# 04_Incense_MCU.net
KiCad netlist of a schematic drawn in Altium Designer
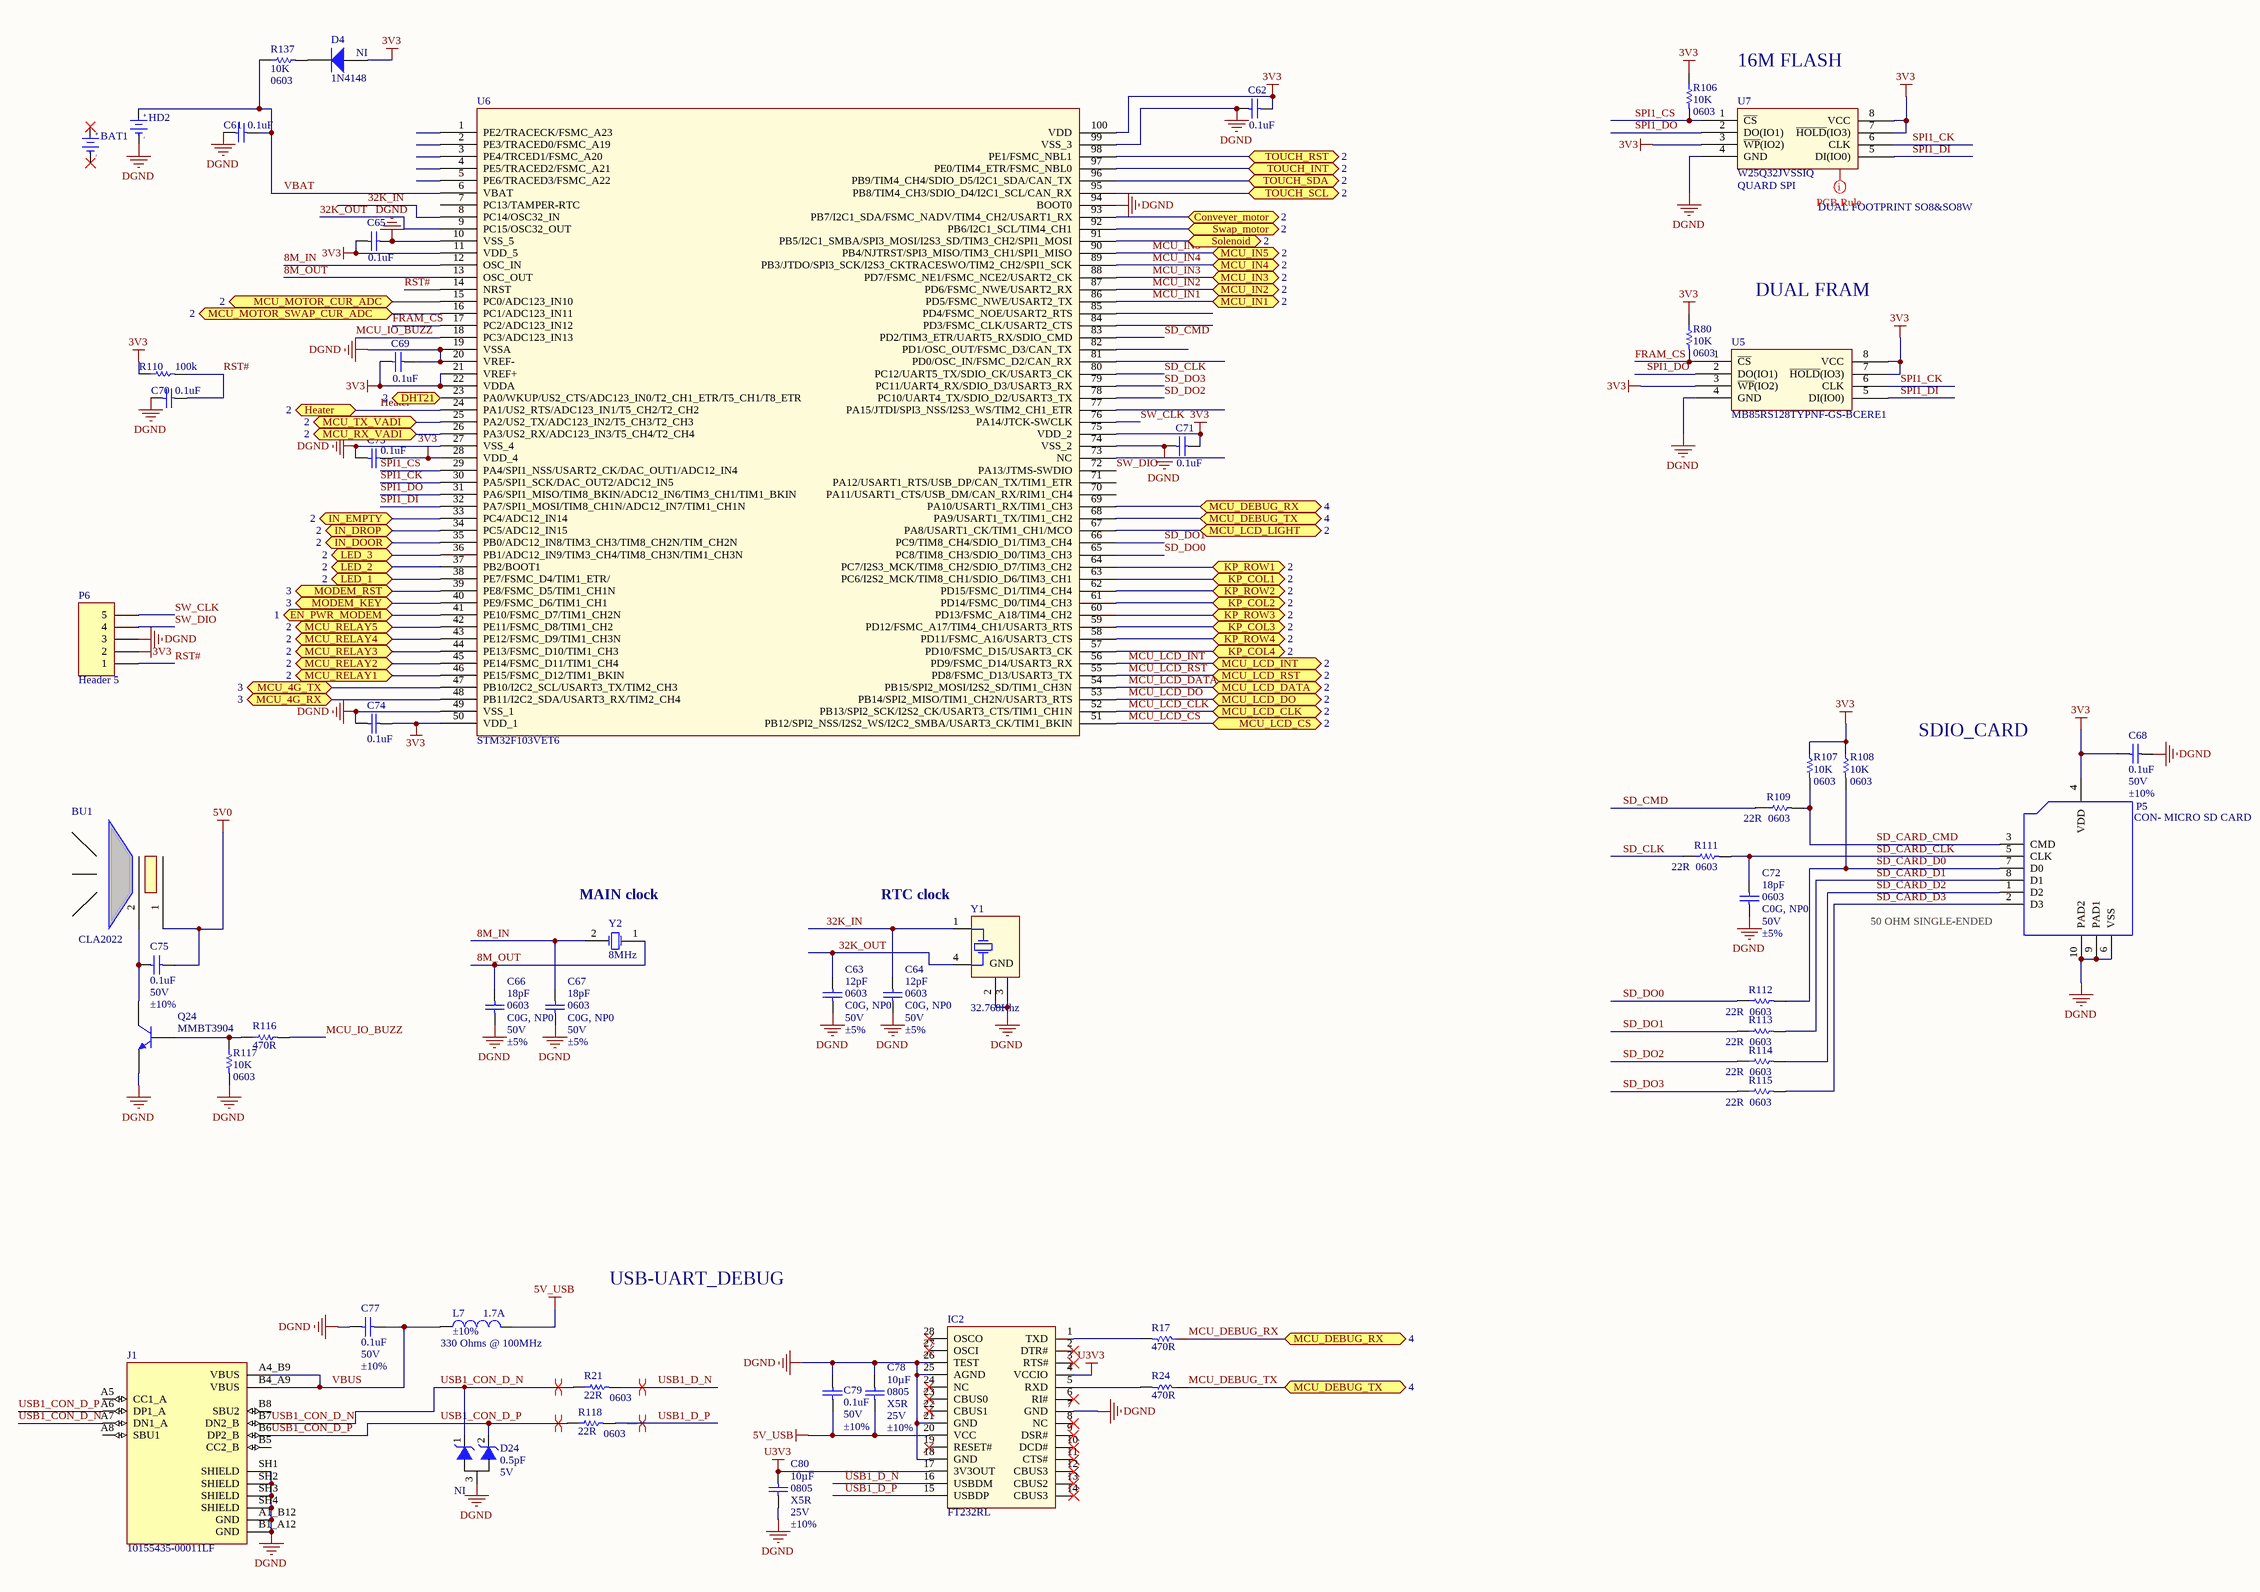
[diagram p0: 04_Incense_MCU.SchDoc]

(export (version "E")
  (design (tool "Eeschema 10.0.6"))
  (components
    (comp (ref "BAT1")
      (value "CR1220")
      (footprint "De Pin Cr1220")
      (description "CR1220 BATTERY")
      (fields (field (name "MANUFACTURER1_PART#") "PIN CR1220 Lithium"))
      (libsource (lib "Schlib1") (part "CR1220 SMD"))
    )
    (comp (ref "BU1")
      (value "CLA2022")
      (footprint "BUZZ_5V_D12X7.5MM")
      (description "BUZZ 5V 12095 12x9.5mm")
      (fields (field (name "MANUFACTURER2_PART#") "5V 9.5x12MM"))
      (libsource (lib "VSM_SES-MAIN_REV04B") (part "PKM13EPYH4000"))
    )
    (comp (ref "C61")
      (value "0.1uF,0805,16v")
      (footprint "CAP 0603")
      (description "CAP CER 0.1UF 50V X7R 0603")
      (fields
        (field (name "=VALUE") "0.1uF")
        (field (name "MANUFACTURER1_PART#") "CL10B104KB8NNNC")
        (field (name "PUBLISHER") "Altium Limited")
      )
      (libsource (lib "Miscellaneous Devices") (part "Cap"))
    )
    (comp (ref "C62")
      (value "Cap")
      (footprint "CAP 0603")
      (description "CAP CER 0.1UF 50V X7R 0603")
      (fields
        (field (name "=VALUE") "0.1uF")
        (field (name "MANUFACTURER1_PART#") "CL10B104KB8NNNC")
        (field (name "PUBLISHER") "Altium Limited")
      )
      (libsource (lib "Miscellaneous Devices") (part "Cap"))
    )
    (comp (ref "C63")
      (value "12pF")
      (footprint "0603")
      (description "CAP-CER,SMD;12PF,5%,50V,C0G/NPO 0603")
      (fields
        (field (name "MATERIAL") "C0G, NP0")
        (field (name "VOLTAGE") "50V")
        (field (name "TOLERANCE") "±5%")
        (field (name "MANUFACTURER1_PART#") "CC0603JRNPO9BN120")
      )
      (libsource (lib "Slider") (part "Cap"))
    )
    (comp (ref "C64")
      (value "12pF")
      (footprint "0603")
      (description "CAP-CER,SMD;12PF,5%,50V,C0G/NPO 0603")
      (fields
        (field (name "MATERIAL") "C0G, NP0")
        (field (name "VOLTAGE") "50V")
        (field (name "TOLERANCE") "±5%")
        (field (name "MANUFACTURER1_PART#") "CC0603JRNPO9BN120")
      )
      (libsource (lib "Slider") (part "Cap"))
    )
    (comp (ref "C65")
      (value "Cap")
      (footprint "cap 0603")
      (description "CAP CER 0.1UF 50V X7R 0603")
      (fields
        (field (name "=VALUE") "0.1uF")
        (field (name "MANUFACTURER1_PART#") "CL10B104KB8NNNC")
        (field (name "PUBLISHER") "Altium Limited")
      )
      (libsource (lib "Miscellaneous Devices") (part "Cap"))
    )
    (comp (ref "C66")
      (value "18pF")
      (footprint "0603")
      (description "CAP CER 18PF 50V C0G/NP0 0603")
      (fields
        (field (name "MATERIAL") "C0G, NP0")
        (field (name "VOLTAGE") "50V")
        (field (name "TOLERANCE") "±5%")
        (field (name "MANUFACTURER1_PART#") "CL10C180JB81PNC")
        (field (name "MANUFACTURER2_PART#") "CC0603JRNPO9BN180")
      )
      (libsource (lib "Slider") (part "Cap"))
    )
    (comp (ref "C67")
      (value "18pF")
      (footprint "0603")
      (description "CAP CER 18PF 50V C0G/NP0 0603")
      (fields
        (field (name "MATERIAL") "C0G, NP0")
        (field (name "VOLTAGE") "50V")
        (field (name "TOLERANCE") "±5%")
        (field (name "MANUFACTURER1_PART#") "CL10C180JB81PNC")
        (field (name "MANUFACTURER2_PART#") "CC0603JRNPO9BN180")
      )
      (libsource (lib "Slider") (part "Cap"))
    )
    (comp (ref "C68")
      (value "0.1uF")
      (footprint "CAP 0603")
      (description "CAP-CER,SMD;0.1UF,10%,50V,X7R,0603")
      (fields
        (field (name "VOLTAGE") "50V")
        (field (name "TOLERANCE") "±10%")
        (field (name "MANUFACTURER1_PART#") "CL10B104KB8NNNC")
        (field (name "MANUFACTURER2_PART#") "M0603X104K050TAX")
      )
      (libsource (lib "Slider") (part "Cap"))
    )
    (comp (ref "C69")
      (value "Cap")
      (footprint "CAP 0603")
      (description "CAP CER 0.1UF 50V X7R 0603")
      (fields
        (field (name "=VALUE") "0.1uF")
        (field (name "MANUFACTURER1_PART#") "CL10B104KB8NNNC")
        (field (name "PUBLISHER") "Altium Limited")
      )
      (libsource (lib "Miscellaneous Devices") (part "Cap"))
    )
    (comp (ref "C70")
      (value "Cap")
      (footprint "CAP 0603")
      (description "CAP CER 0.1UF 50V X7R 0603")
      (fields
        (field (name "=VALUE") "0.1uF")
        (field (name "MANUFACTURER1_PART#") "CL10B104KB8NNNC")
        (field (name "PUBLISHER") "Altium Limited")
      )
      (libsource (lib "Miscellaneous Devices") (part "Cap"))
    )
    (comp (ref "C71")
      (value "0.1uF")
      (footprint "CAP 0603")
      (description "CAP-CER,SMD;0.1UF,10%,50V,X7R,0603")
      (fields
        (field (name "MANUFACTURER1_PART#") "CL10B104KB8NNNC")
        (field (name "Comment") "Cap")
        (field (name "PUBLISHER") "Altium Limited")
      )
      (libsource (lib "Miscellaneous Devices") (part "Cap"))
    )
    (comp (ref "C72")
      (value "18pF")
      (footprint "0603")
      (description "CAP CER 18PF 50V C0G/NP0 0603")
      (fields
        (field (name "MATERIAL") "C0G, NP0")
        (field (name "VOLTAGE") "50V")
        (field (name "TOLERANCE") "±5%")
        (field (name "MANUFACTURER1_PART#") "CL10C180JB81PNC")
        (field (name "MANUFACTURER2_PART#") "CC0603JRNPO9BN180")
      )
      (libsource (lib "Slider") (part "Cap"))
    )
    (comp (ref "C73")
      (value "0.1uF")
      (footprint "CAP 0603")
      (description "CAP-CER,SMD;0.1UF,10%,50V,X7R,0603")
      (fields
        (field (name "MANUFACTURER1_PART#") "CL10B104KB8NNNC")
        (field (name "Comment") "Cap")
        (field (name "PUBLISHER") "Altium Limited")
      )
      (libsource (lib "Miscellaneous Devices") (part "Cap"))
    )
    (comp (ref "C74")
      (value "0.1uF")
      (footprint "CAP 0603")
      (description "CAP-CER,SMD;0.1UF,10%,50V,X7R,0603")
      (fields
        (field (name "MANUFACTURER1_PART#") "CL10B104KB8NNNC")
        (field (name "Comment") "Cap")
        (field (name "PUBLISHER") "Altium Limited")
      )
      (libsource (lib "Miscellaneous Devices") (part "Cap"))
    )
    (comp (ref "C75")
      (value "0.1uF")
      (footprint "CAP 0603")
      (description "CAP-CER,SMD;0.1UF,10%,50V,X7R,0603")
      (fields
        (field (name "VOLTAGE") "50V")
        (field (name "TOLERANCE") "±10%")
        (field (name "MANUFACTURER1_PART#") "CL10B104KB8NNNC")
        (field (name "MANUFACTURER2_PART#") "M0603X104K050TAX")
      )
      (libsource (lib "Slider") (part "Cap"))
    )
    (comp (ref "C77")
      (value "0.1uF")
      (footprint "CAP 0603")
      (description "CAP-CER,SMD;0.1UF,10%,50V,X7R,0603")
      (fields
        (field (name "VOLTAGE") "50V")
        (field (name "TOLERANCE") "±10%")
        (field (name "MANUFACTURER1_PART#") "CL10B104KB8NNNC")
        (field (name "MANUFACTURER2_PART#") "M0603X104K050TAX")
      )
      (libsource (lib "Slider") (part "Cap"))
    )
    (comp (ref "C78")
      (value "10µF")
      (footprint "CAP 0805")
      (description "CAP-CER,SMD;10UF,10%,25V,X5R,0805")
      (fields
        (field (name "MANUFACTURER1_PART#") "TMK212BBJ106KG-T")
        (field (name "MANUFACTURER2_PART#") "CL21A106KAYNNNG")
        (field (name "PACKAGE") "0805")
        (field (name "VOLTAGE") "25V")
        (field (name "TOLERANCE") "±10%")
        (field (name "MATERIAL") "X5R")
      )
      (libsource (lib "Full") (part "Cap-NP-100"))
    )
    (comp (ref "C79")
      (value "0.1uF")
      (footprint "CAP 0603")
      (description "CAP-CER,SMD;0.1UF,10%,50V,X7R,0603")
      (fields
        (field (name "VOLTAGE") "50V")
        (field (name "TOLERANCE") "±10%")
        (field (name "MANUFACTURER1_PART#") "CL10B104KB8NNNC")
        (field (name "MANUFACTURER2_PART#") "M0603X104K050TAX")
      )
      (libsource (lib "Slider") (part "Cap"))
    )
    (comp (ref "C80")
      (value "10µF")
      (footprint "CAP 0805")
      (description "CAP-CER,SMD;10UF,10%,25V,X5R,0805")
      (fields
        (field (name "MANUFACTURER1_PART#") "TMK212BBJ106KG-T")
        (field (name "MANUFACTURER2_PART#") "CL21A106KAYNNNG")
        (field (name "PACKAGE") "0805")
        (field (name "VOLTAGE") "25V")
        (field (name "TOLERANCE") "±10%")
        (field (name "MATERIAL") "X5R")
      )
      (libsource (lib "Full") (part "Cap-NP-100"))
    )
    (comp (ref "D4")
      (value "1N4148")
      (footprint "diode_1206")
      (description "DIODE GP 100V 300MA SOD123 10K")
      (fields
        (field (name "ASSEMBLY") "NI")
        (field (name "MANUFACTURER1_PART#") "1N4148WQ-13-F")
        (field (name "PUBLISHER") "Altium Limited")
      )
      (libsource (lib "Miscellaneous Devices") (part "Diode"))
    )
    (comp (ref "D24")
      (value "ESDR0502BT1G")
      (footprint "SOT-416")
      (description "5V, ESD PROTECTION DEVICES, SOT-23")
      (fields
        (field (name "MANUFACTURER2_PART#") "DF3D6.8MS,LF")
        (field (name "POWER") "320W")
        (field (name "CAPACITANCE") "0.5pF")
        (field (name "VOLTAGE") "5V")
        (field (name "NI_MARK") "NI")
      )
      (libsource (lib "My Library") (part "TVS_DUAL_SIGNAL_5V_SOT23"))
    )
    (comp (ref "HD2")
      (value "CR1220-2ZX")
      (footprint "BATTERY HOLDER CR1220 SMD")
      (description "CR1220 SMD HOLDER")
      (fields (field (name "MANUFACTURER2_PART#") "BH-122A-5"))
      (libsource (lib "Schlib1") (part "CR1220 SMD"))
    )
    (comp (ref "IC2")
      (value "FT232RL")
      (footprint "FT232")
      (description "IC USB FS SERIAL UART 28-SSOP")
      (fields
        (field (name "MANUFACTURER1_PART#") "FT232RL-REEL")
        (field (name "MANUFACTURER2_PART#") "PL2303HX")
      )
      (libsource (lib "PART") (part "PL2303HX"))
    )
    (comp (ref "J1")
      (value "10155435-00011LF")
      (footprint "AMPHENOL_10155435-00011LF")
      (description "USB TYPE C R/A SMT 16PIN")
      (fields (field (name "MF") "Amphenol ICC (FCI)"))
      (libsource (lib "10155435-00011LF") (part "10155435-00011LF"))
    )
    (comp (ref "L7")
      (value "330 Ohms @ 100MHz")
      (footprint "FB 0603")
      (description "FERRITE BEAD 330 OHM 0603 1LN")
      (fields
        (field (name "MANUFACTURER1_PART#") "MPZ1608S331ATA00")
        (field (name "MANUFACTURER2_PART#") "BLM18KG331SN1D")
        (field (name "CURRENT") "1.7A")
        (field (name "TOLERANCE") "±10%")
      )
      (libsource (lib "Full") (part "inductor 2.2uF"))
    )
    (comp (ref "P5")
      (value "CON- MICRO SD CARD")
      (footprint "SD-01A")
      (description "SMD Card Sockets")
      (fields (field (name "MANUFACTURER1_PART#") "SD-01A"))
      (libsource (lib "VDM_V1.0") (part "CON- MICRO SD CARD"))
    )
    (comp (ref "P6")
      (value "Header 5")
      (footprint "HDR1X5")
      (description "Header, 5-Pin,2.54mm")
      (fields (field (name "PUBLISHER") "Altium Limited"))
      (libsource (lib "Miscellaneous Connectors") (part "Header 5"))
    )
    (comp (ref "Q24")
      (value "MMBT3904")
      (footprint "SOT-23")
      (description "NPN 200mA 40V 350mW SOT-23 Transistors")
      (libsource (lib "Miscellaneous Devices") (part "NPN"))
    )
    (comp (ref "R17")
      (value "470R")
      (footprint "res 0603")
      (description "RES SMD, 470 OHM 5% 1/8W 0603")
      (fields
        (field (name "MANUFACTURER1_PART#") "RK73B1JTTD471J")
        (field (name "MANUFACTURER2_PART#") "RMCF0603JT470R")
      )
      (libsource (lib "Full") (part "Res0.3"))
    )
    (comp (ref "R21")
      (value "22R")
      (footprint "res 0603")
      (description "RES 22 OHM 5% 1/10W 0603")
      (fields
        (field (name "MANUFACTURER1_PART#") "RC0603JR-0722RL")
        (field (name "MANUFACTURER2_PART#") "RMCF0603JT22R0")
        (field (name "PCB FOOTPRINT") "0603")
      )
      (libsource (lib "Full") (part "Res0.3"))
    )
    (comp (ref "R24")
      (value "470R")
      (footprint "res 0603")
      (description "RES SMD, 470 OHM 5% 1/8W 0603")
      (fields
        (field (name "MANUFACTURER1_PART#") "RK73B1JTTD471J")
        (field (name "MANUFACTURER2_PART#") "RMCF0603JT470R")
      )
      (libsource (lib "Full") (part "Res0.3"))
    )
    (comp (ref "R80")
      (value "10K")
      (footprint "res 0603")
      (description "RES SMD,10K OHM 5% 1/10W 0603")
      (fields
        (field (name "MANUFACTURER1_PART#") "RMCF0603JT10K0")
        (field (name "MANUFACTURER2_PART#") "R0603J10KKDX")
        (field (name "PCB FOOTPRINT") "0603")
      )
      (libsource (lib "altium-import") (part "root_3_Res0.3_"))
    )
    (comp (ref "R106")
      (value "10K")
      (footprint "res 0603")
      (description "RES SMD,10K OHM 5% 1/10W 0603")
      (fields
        (field (name "MANUFACTURER1_PART#") "RMCF0603JT10K0")
        (field (name "MANUFACTURER2_PART#") "R0603J10KKDX")
        (field (name "PCB FOOTPRINT") "0603")
      )
      (libsource (lib "altium-import") (part "root_3_Res0.3_"))
    )
    (comp (ref "R107")
      (value "10K")
      (footprint "res 0603")
      (description "RES SMD,10K OHM 5% 1/10W 0603")
      (fields
        (field (name "MANUFACTURER1_PART#") "RMCF0603JT10K0")
        (field (name "MANUFACTURER2_PART#") "R0603J10KKDX")
        (field (name "PCB FOOTPRINT") "0603")
      )
      (libsource (lib "altium-import") (part "root_3_Res0.3_"))
    )
    (comp (ref "R108")
      (value "10K")
      (footprint "res 0603")
      (description "RES SMD,10K OHM 5% 1/10W 0603")
      (fields
        (field (name "MANUFACTURER1_PART#") "RMCF0603JT10K0")
        (field (name "MANUFACTURER2_PART#") "R0603J10KKDX")
        (field (name "PCB FOOTPRINT") "0603")
      )
      (libsource (lib "altium-import") (part "root_3_Res0.3_"))
    )
    (comp (ref "R109")
      (value "22R")
      (footprint "res 0603")
      (description "RES 22 OHM 5% 1/10W 0603")
      (fields
        (field (name "MANUFACTURER1_PART#") "RC0603JR-0722RL")
        (field (name "MANUFACTURER2_PART#") "RMCF0603JT22R0")
        (field (name "PCB FOOTPRINT") "0603")
      )
      (libsource (lib "Full") (part "Res0.3"))
    )
    (comp (ref "R110")
      (value "100k")
      (footprint "RES 0603")
      (description "RES 100K OHM 1% 1/10W 0603")
      (fields
        (field (name "MANUFACTURER1_PART#") "RMCF0603FT100K")
        (field (name "Comment") "100k, 0603")
        (field (name "PUBLISHER") "Altium Limited")
      )
      (libsource (lib "Miscellaneous Devices") (part "Res1"))
    )
    (comp (ref "R111")
      (value "22R")
      (footprint "res 0603")
      (description "RES 22 OHM 5% 1/10W 0603")
      (fields
        (field (name "MANUFACTURER1_PART#") "RC0603JR-0722RL")
        (field (name "MANUFACTURER2_PART#") "RMCF0603JT22R0")
        (field (name "PCB FOOTPRINT") "0603")
      )
      (libsource (lib "Full") (part "Res0.3"))
    )
    (comp (ref "R112")
      (value "22R")
      (footprint "res 0603")
      (description "RES 22 OHM 5% 1/10W 0603")
      (fields
        (field (name "MANUFACTURER1_PART#") "RC0603JR-0722RL")
        (field (name "MANUFACTURER2_PART#") "RMCF0603JT22R0")
        (field (name "PCB FOOTPRINT") "0603")
      )
      (libsource (lib "Full") (part "Res0.3"))
    )
    (comp (ref "R113")
      (value "22R")
      (footprint "res 0603")
      (description "RES 22 OHM 5% 1/10W 0603")
      (fields
        (field (name "MANUFACTURER1_PART#") "RC0603JR-0722RL")
        (field (name "MANUFACTURER2_PART#") "RMCF0603JT22R0")
        (field (name "PCB FOOTPRINT") "0603")
      )
      (libsource (lib "Full") (part "Res0.3"))
    )
    (comp (ref "R114")
      (value "22R")
      (footprint "res 0603")
      (description "RES 22 OHM 5% 1/10W 0603")
      (fields
        (field (name "MANUFACTURER1_PART#") "RC0603JR-0722RL")
        (field (name "MANUFACTURER2_PART#") "RMCF0603JT22R0")
        (field (name "PCB FOOTPRINT") "0603")
      )
      (libsource (lib "Full") (part "Res0.3"))
    )
    (comp (ref "R115")
      (value "22R")
      (footprint "res 0603")
      (description "RES 22 OHM 5% 1/10W 0603")
      (fields
        (field (name "MANUFACTURER1_PART#") "RC0603JR-0722RL")
        (field (name "MANUFACTURER2_PART#") "RMCF0603JT22R0")
        (field (name "PCB FOOTPRINT") "0603")
      )
      (libsource (lib "Full") (part "Res0.3"))
    )
    (comp (ref "R116")
      (value "470R")
      (footprint "res 0603")
      (description "RES SMD, 470 OHM 5% 1/8W 0603")
      (fields
        (field (name "MANUFACTURER1_PART#") "RK73B1JTTD471J")
        (field (name "MANUFACTURER2_PART#") "RMCF0603JT470R")
      )
      (libsource (lib "Full") (part "Res0.3"))
    )
    (comp (ref "R117")
      (value "10K")
      (footprint "res 0603")
      (description "RES SMD,10K OHM 5% 1/10W 0603")
      (fields
        (field (name "MANUFACTURER1_PART#") "RMCF0603JT10K0")
        (field (name "MANUFACTURER2_PART#") "R0603J10KKDX")
        (field (name "PCB FOOTPRINT") "0603")
      )
      (libsource (lib "altium-import") (part "root_3_Res0.3_"))
    )
    (comp (ref "R118")
      (value "22R")
      (footprint "res 0603")
      (description "RES 22 OHM 5% 1/10W 0603")
      (fields
        (field (name "MANUFACTURER1_PART#") "RC0603JR-0722RL")
        (field (name "MANUFACTURER2_PART#") "RMCF0603JT22R0")
        (field (name "PCB FOOTPRINT") "0603")
      )
      (libsource (lib "Full") (part "Res0.3"))
    )
    (comp (ref "R137")
      (value "10K")
      (footprint "res 0603")
      (description "RES SMD,10K OHM 5% 1/10W 0603")
      (fields
        (field (name "MANUFACTURER1_PART#") "RMCF0603JT10K0")
        (field (name "MANUFACTURER2_PART#") "R0603J10KKDX")
        (field (name "PCB FOOTPRINT") "0603")
      )
      (libsource (lib "altium-import") (part "root_0_Res0.3_"))
    )
    (comp (ref "U5")
      (value "MB85RS128TYPNF-GS-BCERE1")
      (footprint "SOIC-8")
      (description "IC FRAM 128KBIT SPI 33MHZ 8SOP")
      (fields (field (name "VOLTAGE") "2.7V ~ 3.6V"))
      (libsource (lib "My Library") (part "IC Flash W25Q16JVSNIQ QUAD SO8"))
    )
    (comp (ref "U6")
      (value "STM32F103VET6")
      (footprint "LQFP100_N")
      (description "IC MCU 32BIT 512KB FLASH 100LQFP")
      (libsource (lib "hiendv_sch") (part "STM32F103VET6"))
    )
    (comp (ref "U7")
      (value "W25Q32JVSSIQ")
      (footprint "SOIC-8 208MIL")
      (description "IC FLASH 32MBIT SPI/QUAD 8SOIC")
      (fields (field (name "VOLTAGE") "2.7V ~ 3.6V") (field (name "INTERFACE") "QUARD SPI"))
      (libsource (lib "My Library") (part "IC Flash W25Q16JVSNIQ QUAD SO8"))
    )
    (comp (ref "Y1")
      (value "32.768Khz")
      (footprint "MC-306")
      (description "CRYSTAL 32.7680KHZ 12.5PF SMD")
      (fields (field (name "MANUFACTURER1_PART#") "TKD M8-32.768KHZ-12.5PF-20PPM"))
      (libsource (lib "lib") (part "XT4_32.768KHZ"))
    )
    (comp (ref "Y2")
      (value "8MHz")
      (footprint "xtal_5032")
      (description "CRYSTAL 8.000MHZ 18PF SMD")
      (fields
        (field (name "MANUFACTURER1_PART#") "ABM3-8.000MHZ-J4Q-T")
        (field (name "MANUFACTURER2_PART#") "https://banlinhkien.com/thach-anh-8mhz-smd5032-p6653646.html")
        (field (name "PUBLISHER") "Altium Limited")
      )
      (libsource (lib "Miscellaneous Devices") (part "XTAL"))
    )
  )
  (nets
    (net (code "1") (name "/8M_IN") (class "Default")
      (node (ref "C67") (pin "1") (pinfunction "1_1") (pintype "passive"))
      (node (ref "U6") (pin "12") (pinfunction "OSC_IN_12") (pintype "passive"))
      (node (ref "Y2") (pin "2") (pinfunction "OSC2_2") (pintype "passive"))
    )
    (net (code "2") (name "/8M_OUT") (class "Default")
      (node (ref "C66") (pin "1") (pinfunction "1_1") (pintype "passive"))
      (node (ref "U6") (pin "13") (pinfunction "OSC_OUT_13") (pintype "passive"))
      (node (ref "Y2") (pin "1") (pinfunction "OSC1_1") (pintype "passive"))
    )
    (net (code "3") (name "/32K_IN") (class "Default")
      (node (ref "C64") (pin "1") (pinfunction "1_1") (pintype "passive"))
      (node (ref "U6") (pin "8") (pinfunction "PC14/OSC32_IN_8") (pintype "passive"))
      (node (ref "Y1") (pin "1") (pinfunction "XTAL_1") (pintype "passive"))
    )
    (net (code "4") (name "/32K_OUT") (class "Default")
      (node (ref "C63") (pin "1") (pinfunction "1_1") (pintype "passive"))
      (node (ref "U6") (pin "9") (pinfunction "PC15/OSC32_OUT_9") (pintype "passive"))
      (node (ref "Y1") (pin "4") (pinfunction "XTAL_4") (pintype "passive"))
    )
    (net (code "5") (name "/Conveyer_motor") (class "Default")
      (node (ref "U6") (pin "93") (pinfunction "PB7/I2C1_SDA/FSMC_NADV/TIM4_CH2/USART1_RX_93") (pintype "passive"))
    )
    (net (code "6") (name "/DHT21") (class "Default")
      (node (ref "U6") (pin "23") (pinfunction "PA0/WKUP/US2_CTS/ADC123_IN0/T2_CH1_ETR/T5_CH1/T8_ETR_23") (pintype "passive"))
    )
    (net (code "7") (name "/EN_PWR_MODEM") (class "Default")
      (node (ref "U6") (pin "41") (pinfunction "PE10/FSMC_D7/TIM1_CH2N_41") (pintype "passive"))
    )
    (net (code "8") (name "/FRAM_CS") (class "Default")
      (node (ref "R80") (pin "2") (pinfunction "2_2") (pintype "passive"))
      (node (ref "U5") (pin "1") (pinfunction "~{CS}_1") (pintype "passive"))
      (node (ref "U6") (pin "17") (pinfunction "PC2/ADC123_IN12_17") (pintype "passive"))
    )
    (net (code "9") (name "/Heater") (class "Default")
      (node (ref "U6") (pin "24") (pinfunction "PA1/US2_RTS/ADC123_IN1/T5_CH2/T2_CH2_24") (pintype "passive"))
    )
    (net (code "10") (name "/IN_DOOR") (class "Default")
      (node (ref "U6") (pin "35") (pinfunction "PB0/ADC12_IN8/TIM3_CH3/TIM8_CH2N/TIM_CH2N_35") (pintype "passive"))
    )
    (net (code "11") (name "/IN_DROP") (class "Default")
      (node (ref "U6") (pin "34") (pinfunction "PC5/ADC12_IN15_34") (pintype "passive"))
    )
    (net (code "12") (name "/IN_EMPTY") (class "Default")
      (node (ref "U6") (pin "33") (pinfunction "PC4/ADC12_IN14_33") (pintype "passive"))
    )
    (net (code "13") (name "/KP_COL1") (class "Default")
      (node (ref "U6") (pin "63") (pinfunction "PC6/I2S2_MCK/TIM8_CH1/SDIO_D6/TIM3_CH1_63") (pintype "passive"))
    )
    (net (code "14") (name "/KP_COL2") (class "Default")
      (node (ref "U6") (pin "61") (pinfunction "PD14/FSMC_D0/TIM4_CH3_61") (pintype "passive"))
    )
    (net (code "15") (name "/KP_COL3") (class "Default")
      (node (ref "U6") (pin "59") (pinfunction "PD12/FSMC_A17/TIM4_CH1/USART3_RTS_59") (pintype "passive"))
    )
    (net (code "16") (name "/KP_COL4") (class "Default")
      (node (ref "U6") (pin "57") (pinfunction "PD10/FSMC_D15/USART3_CK_57") (pintype "passive"))
    )
    (net (code "17") (name "/KP_ROW1") (class "Default")
      (node (ref "U6") (pin "64") (pinfunction "PC7/I2S3_MCK/TIM8_CH2/SDIO_D7/TIM3_CH2_64") (pintype "passive"))
    )
    (net (code "18") (name "/KP_ROW2") (class "Default")
      (node (ref "U6") (pin "62") (pinfunction "PD15/FSMC_D1/TIM4_CH4_62") (pintype "passive"))
    )
    (net (code "19") (name "/KP_ROW3") (class "Default")
      (node (ref "U6") (pin "60") (pinfunction "PD13/FSMC_A18/TIM4_CH2_60") (pintype "passive"))
    )
    (net (code "20") (name "/KP_ROW4") (class "Default")
      (node (ref "U6") (pin "58") (pinfunction "PD11/FSMC_A16/USART3_CTS_58") (pintype "passive"))
    )
    (net (code "21") (name "/LED_1") (class "Default")
      (node (ref "U6") (pin "38") (pinfunction "PE7/FSMC_D4/TIM1_ETR/_38") (pintype "passive"))
    )
    (net (code "22") (name "/LED_2") (class "Default")
      (node (ref "U6") (pin "37") (pinfunction "PB2/BOOT1_37") (pintype "passive"))
    )
    (net (code "23") (name "/LED_3") (class "Default")
      (node (ref "U6") (pin "36") (pinfunction "PB1/ADC12_IN9/TIM3_CH4/TIM8_CH3N/TIM1_CH3N_36") (pintype "passive"))
    )
    (net (code "24") (name "/MCU_4G_RX") (class "Default")
      (node (ref "U6") (pin "48") (pinfunction "PB11/I2C2_SDA/USART3_RX/TIM2_CH4_48") (pintype "passive"))
    )
    (net (code "25") (name "/MCU_4G_TX") (class "Default")
      (node (ref "U6") (pin "47") (pinfunction "PB10/I2C2_SCL/USART3_TX/TIM2_CH3_47") (pintype "passive"))
    )
    (net (code "26") (name "/MCU_DEBUG_RX") (class "Default")
      (node (ref "R17") (pin "1") (pinfunction "1_1") (pintype "passive"))
      (node (ref "U6") (pin "69") (pinfunction "PA10/USART1_RX/TIM1_CH3_69") (pintype "passive"))
    )
    (net (code "27") (name "/MCU_DEBUG_TX") (class "Default")
      (node (ref "R24") (pin "1") (pinfunction "1_1") (pintype "passive"))
      (node (ref "U6") (pin "68") (pinfunction "PA9/USART1_TX/TIM1_CH2_68") (pintype "passive"))
    )
    (net (code "28") (name "/MCU_IN1") (class "Default")
      (node (ref "U6") (pin "86") (pinfunction "PD5/FSMC_NWE/USART2_TX_86") (pintype "passive"))
    )
    (net (code "29") (name "/MCU_IN2") (class "Default")
      (node (ref "U6") (pin "87") (pinfunction "PD6/FSMC_NWE/USART2_RX_87") (pintype "passive"))
    )
    (net (code "30") (name "/MCU_IN3") (class "Default")
      (node (ref "U6") (pin "88") (pinfunction "PD7/FSMC_NE1/FSMC_NCE2/USART2_CK_88") (pintype "passive"))
    )
    (net (code "31") (name "/MCU_IN4") (class "Default")
      (node (ref "U6") (pin "89") (pinfunction "PB3/JTDO/SPI3_SCK/I2S3_CKTRACESWO/TIM2_CH2/SPI1_SCK_89") (pintype "passive"))
    )
    (net (code "32") (name "/MCU_IN5") (class "Default")
      (node (ref "U6") (pin "90") (pinfunction "PB4/NJTRST/SPI3_MISO/TIM3_CH1/SPI1_MISO_90") (pintype "passive"))
    )
    (net (code "33") (name "/MCU_IO_BUZZ") (class "Default")
      (node (ref "R116") (pin "2") (pinfunction "2_2") (pintype "passive"))
      (node (ref "U6") (pin "18") (pinfunction "PC3/ADC123_IN13_18") (pintype "passive"))
    )
    (net (code "34") (name "/MCU_LCD_CLK") (class "Default")
      (node (ref "U6") (pin "52") (pinfunction "PB13/SPI2_SCK/I2S2_CK/USART3_CTS/TIM1_CH1N_52") (pintype "passive"))
    )
    (net (code "35") (name "/MCU_LCD_CS") (class "Default")
      (node (ref "U6") (pin "51") (pinfunction "PB12/SPI2_NSS/I2S2_WS/I2C2_SMBA/USART3_CK/TIM1_BKIN_51") (pintype "passive"))
    )
    (net (code "36") (name "/MCU_LCD_DATA") (class "Default")
      (node (ref "U6") (pin "54") (pinfunction "PB15/SPI2_MOSI/I2S2_SD/TIM1_CH3N_54") (pintype "passive"))
    )
    (net (code "37") (name "/MCU_LCD_DO") (class "Default")
      (node (ref "U6") (pin "53") (pinfunction "PB14/SPI2_MISO/TIM1_CH2N/USART3_RTS_53") (pintype "passive"))
    )
    (net (code "38") (name "/MCU_LCD_INT") (class "Default")
      (node (ref "U6") (pin "56") (pinfunction "PD9/FSMC_D14/USART3_RX_56") (pintype "passive"))
    )
    (net (code "39") (name "/MCU_LCD_LIGHT") (class "Default")
      (node (ref "U6") (pin "67") (pinfunction "PA8/USART1_CK/TIM1_CH1/MCO_67") (pintype "passive"))
    )
    (net (code "40") (name "/MCU_LCD_RST") (class "Default")
      (node (ref "U6") (pin "55") (pinfunction "PD8/FSMC_D13/USART3_TX_55") (pintype "passive"))
    )
    (net (code "41") (name "/MCU_MOTOR_CUR_ADC") (class "Default")
      (node (ref "U6") (pin "15") (pinfunction "PC0/ADC123_IN10_15") (pintype "passive"))
    )
    (net (code "42") (name "/MCU_MOTOR_SWAP_CUR_ADC") (class "Default")
      (node (ref "U6") (pin "16") (pinfunction "PC1/ADC123_IN11_16") (pintype "passive"))
    )
    (net (code "43") (name "/MCU_RELAY1") (class "Default")
      (node (ref "U6") (pin "46") (pinfunction "PE15/FSMC_D12/TIM1_BKIN_46") (pintype "passive"))
    )
    (net (code "44") (name "/MCU_RELAY2") (class "Default")
      (node (ref "U6") (pin "45") (pinfunction "PE14/FSMC_D11/TIM1_CH4_45") (pintype "passive"))
    )
    (net (code "45") (name "/MCU_RELAY3") (class "Default")
      (node (ref "U6") (pin "44") (pinfunction "PE13/FSMC_D10/TIM1_CH3_44") (pintype "passive"))
    )
    (net (code "46") (name "/MCU_RELAY4") (class "Default")
      (node (ref "U6") (pin "43") (pinfunction "PE12/FSMC_D9/TIM1_CH3N_43") (pintype "passive"))
    )
    (net (code "47") (name "/MCU_RELAY5") (class "Default")
      (node (ref "U6") (pin "42") (pinfunction "PE11/FSMC_D8/TIM1_CH2_42") (pintype "passive"))
    )
    (net (code "48") (name "/MCU_RX_VADI") (class "Default")
      (node (ref "U6") (pin "26") (pinfunction "PA3/US2_RX/ADC123_IN3/T5_CH4/T2_CH4_26") (pintype "passive"))
    )
    (net (code "49") (name "/MCU_TX_VADI") (class "Default")
      (node (ref "U6") (pin "25") (pinfunction "PA2/US2_TX/ADC123_IN2/T5_CH3/T2_CH3_25") (pintype "passive"))
    )
    (net (code "50") (name "/MODEM_KEY") (class "Default")
      (node (ref "U6") (pin "40") (pinfunction "PE9/FSMC_D6/TIM1_CH1_40") (pintype "passive"))
    )
    (net (code "51") (name "/MODEM_RST") (class "Default")
      (node (ref "U6") (pin "39") (pinfunction "PE8/FSMC_D5/TIM1_CH1N_39") (pintype "passive"))
    )
    (net (code "52") (name "/RST#") (class "Default")
      (node (ref "C70") (pin "2") (pinfunction "2_2") (pintype "passive"))
      (node (ref "P6") (pin "1") (pinfunction "1_1") (pintype "passive"))
      (node (ref "R110") (pin "2") (pinfunction "2_2") (pintype "passive"))
      (node (ref "U6") (pin "14") (pinfunction "NRST_14") (pintype "passive"))
    )
    (net (code "53") (name "/SD_CARD_CLK") (class "Default")
      (node (ref "C72") (pin "1") (pinfunction "1_1") (pintype "passive"))
      (node (ref "P5") (pin "5") (pinfunction "CLK_5") (pintype "passive"))
      (node (ref "R111") (pin "2") (pinfunction "2_2") (pintype "passive"))
    )
    (net (code "54") (name "/SD_CARD_CMD") (class "Default")
      (node (ref "P5") (pin "3") (pinfunction "CMD_3") (pintype "passive"))
      (node (ref "R107") (pin "2") (pinfunction "2_2") (pintype "passive"))
      (node (ref "R109") (pin "2") (pinfunction "2_2") (pintype "passive"))
    )
    (net (code "55") (name "/SD_CARD_D0") (class "Default")
      (node (ref "P5") (pin "7") (pinfunction "D0_7") (pintype "passive"))
      (node (ref "R108") (pin "2") (pinfunction "2_2") (pintype "passive"))
      (node (ref "R112") (pin "2") (pinfunction "2_2") (pintype "passive"))
    )
    (net (code "56") (name "/SD_CARD_D1") (class "Default")
      (node (ref "P5") (pin "8") (pinfunction "D1_8") (pintype "passive"))
      (node (ref "R113") (pin "2") (pinfunction "2_2") (pintype "passive"))
    )
    (net (code "57") (name "/SD_CARD_D2") (class "Default")
      (node (ref "P5") (pin "1") (pinfunction "D2_1") (pintype "passive"))
      (node (ref "R114") (pin "2") (pinfunction "2_2") (pintype "passive"))
    )
    (net (code "58") (name "/SD_CARD_D3") (class "Default")
      (node (ref "P5") (pin "2") (pinfunction "D3_2") (pintype "passive"))
      (node (ref "R115") (pin "2") (pinfunction "2_2") (pintype "passive"))
    )
    (net (code "59") (name "/SD_CLK") (class "Default")
      (node (ref "R111") (pin "1") (pinfunction "1_1") (pintype "passive"))
      (node (ref "U6") (pin "80") (pinfunction "PC12/UART5_TX/SDIO_CK/USART3_CK_80") (pintype "passive"))
    )
    (net (code "60") (name "/SD_CMD") (class "Default")
      (node (ref "R109") (pin "1") (pinfunction "1_1") (pintype "passive"))
      (node (ref "U6") (pin "83") (pinfunction "PD2/TIM3_ETR/UART5_RX/SDIO_CMD_83") (pintype "passive"))
    )
    (net (code "61") (name "/SD_DO0") (class "Default")
      (node (ref "R112") (pin "1") (pinfunction "1_1") (pintype "passive"))
      (node (ref "U6") (pin "65") (pinfunction "PC8/TIM8_CH3/SDIO_D0/TIM3_CH3_65") (pintype "passive"))
    )
    (net (code "62") (name "/SD_DO1") (class "Default")
      (node (ref "R113") (pin "1") (pinfunction "1_1") (pintype "passive"))
      (node (ref "U6") (pin "66") (pinfunction "PC9/TIM8_CH4/SDIO_D1/TIM3_CH4_66") (pintype "passive"))
    )
    (net (code "63") (name "/SD_DO2") (class "Default")
      (node (ref "R114") (pin "1") (pinfunction "1_1") (pintype "passive"))
      (node (ref "U6") (pin "78") (pinfunction "PC10/UART4_TX/SDIO_D2/USART3_TX_78") (pintype "passive"))
    )
    (net (code "64") (name "/SD_DO3") (class "Default")
      (node (ref "R115") (pin "1") (pinfunction "1_1") (pintype "passive"))
      (node (ref "U6") (pin "79") (pinfunction "PC11/UART4_RX/SDIO_D3/USART3_RX_79") (pintype "passive"))
    )
    (net (code "65") (name "/SPI1_CK") (class "Default")
      (node (ref "U5") (pin "6") (pinfunction "CLK_6") (pintype "passive"))
      (node (ref "U6") (pin "30") (pinfunction "PA5/SPI1_SCK/DAC_OUT2/ADC12_IN5_30") (pintype "passive"))
      (node (ref "U7") (pin "6") (pinfunction "CLK_6") (pintype "passive"))
    )
    (net (code "66") (name "/SPI1_CS") (class "Default")
      (node (ref "R106") (pin "2") (pinfunction "2_2") (pintype "passive"))
      (node (ref "U6") (pin "29") (pinfunction "PA4/SPI1_NSS/USART2_CK/DAC_OUT1/ADC12_IN4_29") (pintype "passive"))
      (node (ref "U7") (pin "1") (pinfunction "~{CS}_1") (pintype "passive"))
    )
    (net (code "67") (name "/SPI1_DI") (class "Default")
      (node (ref "U5") (pin "5") (pinfunction "DI(IO0)_5") (pintype "passive"))
      (node (ref "U6") (pin "32") (pinfunction "PA7/SPI1_MOSI/TIM8_CH1N/ADC12_IN7/TIM1_CH1N_32") (pintype "passive"))
      (node (ref "U7") (pin "5") (pinfunction "DI(IO0)_5") (pintype "passive"))
    )
    (net (code "68") (name "/SPI1_DO") (class "Default")
      (node (ref "U5") (pin "2") (pinfunction "DO(IO1)_2") (pintype "passive"))
      (node (ref "U6") (pin "31") (pinfunction "PA6/SPI1_MISO/TIM8_BKIN/ADC12_IN6/TIM3_CH1/TIM1_BKIN_31") (pintype "passive"))
      (node (ref "U7") (pin "2") (pinfunction "DO(IO1)_2") (pintype "passive"))
    )
    (net (code "69") (name "/SW_CLK") (class "Default")
      (node (ref "P6") (pin "5") (pinfunction "5_5") (pintype "passive"))
      (node (ref "U6") (pin "76") (pinfunction "PA14/JTCK-SWCLK_76") (pintype "passive"))
    )
    (net (code "70") (name "/SW_DIO") (class "Default")
      (node (ref "P6") (pin "4") (pinfunction "4_4") (pintype "passive"))
      (node (ref "U6") (pin "72") (pinfunction "PA13/JTMS-SWDIO_72") (pintype "passive"))
    )
    (net (code "71") (name "/Solenoid") (class "Default")
      (node (ref "U6") (pin "91") (pinfunction "PB5/I2C1_SMBA/SPI3_MOSI/I2S3_SD/TIM3_CH2/SPI1_MOSI_91") (pintype "passive"))
    )
    (net (code "72") (name "/Swap_motor") (class "Default")
      (node (ref "U6") (pin "92") (pinfunction "PB6/I2C1_SCL/TIM4_CH1_92") (pintype "passive"))
    )
    (net (code "73") (name "/TOUCH_INT") (class "Default")
      (node (ref "U6") (pin "97") (pinfunction "PE0/TIM4_ETR/FSMC_NBL0_97") (pintype "passive"))
    )
    (net (code "74") (name "/TOUCH_RST") (class "Default")
      (node (ref "U6") (pin "98") (pinfunction "PE1/FSMC_NBL1_98") (pintype "passive"))
    )
    (net (code "75") (name "/TOUCH_SCL") (class "Default")
      (node (ref "U6") (pin "95") (pinfunction "PB8/TIM4_CH3/SDIO_D4/I2C1_SCL/CAN_RX_95") (pintype "passive"))
    )
    (net (code "76") (name "/TOUCH_SDA") (class "Default")
      (node (ref "U6") (pin "96") (pinfunction "PB9/TIM4_CH4/SDIO_D5/I2C1_SDA/CAN_TX_96") (pintype "passive"))
    )
    (net (code "77") (name "/USB1_CON_D_N") (class "Default")
      (node (ref "D24") (pin "1") (pinfunction "K_1") (pintype "passive"))
      (node (ref "J1") (pin "A7") (pinfunction "DN1_A_A7") (pintype "bidirectional"))
      (node (ref "J1") (pin "B7") (pinfunction "DN2_B_B7") (pintype "bidirectional"))
      (node (ref "R21") (pin "1") (pinfunction "1_1") (pintype "passive"))
    )
    (net (code "78") (name "/USB1_CON_D_P") (class "Default")
      (node (ref "D24") (pin "2") (pinfunction "K_2") (pintype "passive"))
      (node (ref "J1") (pin "A6") (pinfunction "DP1_A_A6") (pintype "bidirectional"))
      (node (ref "J1") (pin "B6") (pinfunction "DP2_B_B6") (pintype "bidirectional"))
      (node (ref "R118") (pin "1") (pinfunction "1_1") (pintype "passive"))
    )
    (net (code "79") (name "/USB1_D_N") (class "Default")
      (node (ref "IC2") (pin "16") (pinfunction "USBDM_16") (pintype "passive"))
      (node (ref "R21") (pin "2") (pinfunction "2_2") (pintype "passive"))
    )
    (net (code "80") (name "/USB1_D_P") (class "Default")
      (node (ref "IC2") (pin "15") (pinfunction "USBDP_15") (pintype "passive"))
      (node (ref "R118") (pin "2") (pinfunction "2_2") (pintype "passive"))
    )
    (net (code "81") (name "/VBAT") (class "Default")
      (node (ref "C61") (pin "2") (pinfunction "2_2") (pintype "passive"))
      (node (ref "HD2") (pin "1") (pinfunction "+3V_1") (pintype "passive"))
      (node (ref "R137") (pin "1") (pinfunction "1_1") (pintype "passive"))
      (node (ref "U6") (pin "6") (pinfunction "VBAT_6") (pintype "passive"))
    )
    (net (code "82") (name "/VBUS") (class "Default")
      (node (ref "C77") (pin "2") (pinfunction "2_2") (pintype "passive"))
      (node (ref "J1") (pin "A4_B9") (pinfunction "VBUS_A4_B9") (pintype "power_in"))
      (node (ref "J1") (pin "B4_A9") (pinfunction "VBUS_B4_A9") (pintype "power_in"))
      (node (ref "L7") (pin "1") (pinfunction "1_1") (pintype "passive"))
    )
    (net (code "83") (name "3V3") (class "Default")
      (node (ref "C62") (pin "2") (pinfunction "2_2") (pintype "passive"))
      (node (ref "C65") (pin "1") (pinfunction "1_1") (pintype "passive"))
      (node (ref "C68") (pin "1") (pinfunction "1_1") (pintype "passive"))
      (node (ref "C69") (pin "1") (pinfunction "1_1") (pintype "passive"))
      (node (ref "C71") (pin "2") (pinfunction "2_2") (pintype "passive"))
      (node (ref "C73") (pin "1") (pinfunction "1_1") (pintype "passive"))
      (node (ref "C74") (pin "1") (pinfunction "1_1") (pintype "passive"))
      (node (ref "D4") (pin "1") (pinfunction "A_1") (pintype "passive"))
      (node (ref "P5") (pin "4") (pinfunction "VDD_4") (pintype "passive"))
      (node (ref "P6") (pin "2") (pinfunction "2_2") (pintype "passive"))
      (node (ref "R106") (pin "1") (pinfunction "1_1") (pintype "passive"))
      (node (ref "R107") (pin "1") (pinfunction "1_1") (pintype "passive"))
      (node (ref "R108") (pin "1") (pinfunction "1_1") (pintype "passive"))
      (node (ref "R110") (pin "1") (pinfunction "1_1") (pintype "passive"))
      (node (ref "R80") (pin "1") (pinfunction "1_1") (pintype "passive"))
      (node (ref "U5") (pin "3") (pinfunction "~{WP}(IO2)_3") (pintype "passive"))
      (node (ref "U5") (pin "7") (pinfunction "~{HOLD}(IO3)_7") (pintype "passive"))
      (node (ref "U5") (pin "8") (pinfunction "VCC_8") (pintype "passive"))
      (node (ref "U6") (pin "100") (pinfunction "VDD_100") (pintype "passive"))
      (node (ref "U6") (pin "11") (pinfunction "VDD_5_11") (pintype "passive"))
      (node (ref "U6") (pin "21") (pinfunction "VREF+_21") (pintype "passive"))
      (node (ref "U6") (pin "22") (pinfunction "VDDA_22") (pintype "passive"))
      (node (ref "U6") (pin "28") (pinfunction "VDD_4_28") (pintype "passive"))
      (node (ref "U6") (pin "50") (pinfunction "VDD_1_50") (pintype "passive"))
      (node (ref "U6") (pin "75") (pinfunction "VDD_2_75") (pintype "passive"))
      (node (ref "U7") (pin "3") (pinfunction "~{WP}(IO2)_3") (pintype "passive"))
      (node (ref "U7") (pin "7") (pinfunction "~{HOLD}(IO3)_7") (pintype "passive"))
      (node (ref "U7") (pin "8") (pinfunction "VCC_8") (pintype "passive"))
    )
    (net (code "84") (name "5V0") (class "Default")
      (node (ref "BU1") (pin "1") (pinfunction "PIN1_1") (pintype "passive"))
      (node (ref "C75") (pin "2") (pinfunction "2_2") (pintype "passive"))
    )
    (net (code "85") (name "5V_USB") (class "Default")
      (node (ref "C78") (pin "2") (pinfunction "2_2") (pintype "passive"))
      (node (ref "C79") (pin "1") (pinfunction "1_1") (pintype "passive"))
      (node (ref "IC2") (pin "20") (pinfunction "VCC_20") (pintype "passive"))
      (node (ref "L7") (pin "2") (pinfunction "2_2") (pintype "passive"))
    )
    (net (code "86") (name "DGND") (class "Default")
      (node (ref "C61") (pin "1") (pinfunction "1_1") (pintype "passive"))
      (node (ref "C62") (pin "1") (pinfunction "1_1") (pintype "passive"))
      (node (ref "C63") (pin "2") (pinfunction "2_2") (pintype "passive"))
      (node (ref "C64") (pin "2") (pinfunction "2_2") (pintype "passive"))
      (node (ref "C65") (pin "2") (pinfunction "2_2") (pintype "passive"))
      (node (ref "C66") (pin "2") (pinfunction "2_2") (pintype "passive"))
      (node (ref "C67") (pin "2") (pinfunction "2_2") (pintype "passive"))
      (node (ref "C68") (pin "2") (pinfunction "2_2") (pintype "passive"))
      (node (ref "C69") (pin "2") (pinfunction "2_2") (pintype "passive"))
      (node (ref "C70") (pin "1") (pinfunction "1_1") (pintype "passive"))
      (node (ref "C71") (pin "1") (pinfunction "1_1") (pintype "passive"))
      (node (ref "C72") (pin "2") (pinfunction "2_2") (pintype "passive"))
      (node (ref "C73") (pin "2") (pinfunction "2_2") (pintype "passive"))
      (node (ref "C74") (pin "2") (pinfunction "2_2") (pintype "passive"))
      (node (ref "C77") (pin "1") (pinfunction "1_1") (pintype "passive"))
      (node (ref "C78") (pin "1") (pinfunction "1_1") (pintype "passive"))
      (node (ref "C79") (pin "2") (pinfunction "2_2") (pintype "passive"))
      (node (ref "C80") (pin "2") (pinfunction "2_2") (pintype "passive"))
      (node (ref "D24") (pin "3") (pinfunction "A_3") (pintype "passive"))
      (node (ref "HD2") (pin "2") (pinfunction "GND_2") (pintype "passive"))
      (node (ref "IC2") (pin "18") (pinfunction "GND_18") (pintype "passive"))
      (node (ref "IC2") (pin "21") (pinfunction "GND_21") (pintype "passive"))
      (node (ref "IC2") (pin "25") (pinfunction "AGND_25") (pintype "passive"))
      (node (ref "IC2") (pin "26") (pinfunction "TEST_26") (pintype "passive"))
      (node (ref "IC2") (pin "7") (pinfunction "GND_7") (pintype "passive"))
      (node (ref "J1") (pin "A1_B12") (pinfunction "GND_A1_B12") (pintype "power_in"))
      (node (ref "J1") (pin "B1_A12") (pinfunction "GND_B1_A12") (pintype "power_in"))
      (node (ref "J1") (pin "SH1") (pinfunction "SHIELD_SH1") (pintype "passive"))
      (node (ref "J1") (pin "SH2") (pinfunction "SHIELD_SH2") (pintype "passive"))
      (node (ref "J1") (pin "SH3") (pinfunction "SHIELD_SH3") (pintype "passive"))
      (node (ref "J1") (pin "SH4") (pinfunction "SHIELD_SH4") (pintype "passive"))
      (node (ref "P5") (pin "10") (pinfunction "PAD2_10") (pintype "passive"))
      (node (ref "P5") (pin "6") (pinfunction "VSS_6") (pintype "passive"))
      (node (ref "P5") (pin "9") (pinfunction "PAD1_9") (pintype "passive"))
      (node (ref "P6") (pin "3") (pinfunction "3_3") (pintype "passive"))
      (node (ref "Q24") (pin "2") (pinfunction "E_2") (pintype "passive"))
      (node (ref "R117") (pin "2") (pinfunction "2_2") (pintype "passive"))
      (node (ref "U5") (pin "4") (pinfunction "GND_4") (pintype "passive"))
      (node (ref "U6") (pin "10") (pinfunction "VSS_5_10") (pintype "passive"))
      (node (ref "U6") (pin "19") (pinfunction "VSSA_19") (pintype "passive"))
      (node (ref "U6") (pin "20") (pinfunction "VREF-_20") (pintype "passive"))
      (node (ref "U6") (pin "27") (pinfunction "VSS_4_27") (pintype "passive"))
      (node (ref "U6") (pin "49") (pinfunction "VSS_1_49") (pintype "passive"))
      (node (ref "U6") (pin "74") (pinfunction "VSS_2_74") (pintype "passive"))
      (node (ref "U6") (pin "94") (pinfunction "BOOT0_94") (pintype "passive"))
      (node (ref "U6") (pin "99") (pinfunction "VSS_3_99") (pintype "passive"))
      (node (ref "U7") (pin "4") (pinfunction "GND_4") (pintype "passive"))
      (node (ref "Y1") (pin "2") (pinfunction "GND_2") (pintype "passive"))
      (node (ref "Y1") (pin "3") (pinfunction "GND_3") (pintype "passive"))
    )
    (net (code "87") (name "Net-(BU1-PIN2)") (class "Default")
      (node (ref "BU1") (pin "2") (pinfunction "PIN2_2") (pintype "passive"))
      (node (ref "C75") (pin "1") (pinfunction "1_1") (pintype "passive"))
      (node (ref "Q24") (pin "3") (pinfunction "C_3") (pintype "passive"))
    )
    (net (code "88") (name "Net-(D4-K)") (class "Default")
      (node (ref "D4") (pin "2") (pinfunction "K_2") (pintype "passive"))
      (node (ref "R137") (pin "2") (pinfunction "2_2") (pintype "passive"))
    )
    (net (code "89") (name "Net-(IC2-RXD)") (class "Default")
      (node (ref "IC2") (pin "5") (pinfunction "RXD_5") (pintype "passive"))
      (node (ref "R24") (pin "2") (pinfunction "2_2") (pintype "passive"))
    )
    (net (code "90") (name "Net-(IC2-TXD)") (class "Default")
      (node (ref "IC2") (pin "1") (pinfunction "TXD_1") (pintype "passive"))
      (node (ref "R17") (pin "2") (pinfunction "2_2") (pintype "passive"))
    )
    (net (code "91") (name "Net-(Q24-B)") (class "Default")
      (node (ref "Q24") (pin "1") (pinfunction "B_1") (pintype "passive"))
      (node (ref "R116") (pin "1") (pinfunction "1_1") (pintype "passive"))
      (node (ref "R117") (pin "1") (pinfunction "1_1") (pintype "passive"))
    )
    (net (code "92") (name "U3V3") (class "Default")
      (node (ref "C80") (pin "1") (pinfunction "1_1") (pintype "passive"))
      (node (ref "IC2") (pin "17") (pinfunction "3V3OUT_17") (pintype "passive"))
      (node (ref "IC2") (pin "4") (pinfunction "VCCIO_4") (pintype "passive"))
    )
    (net (code "93") (name "unconnected-(BAT1-+3V-Pad1)") (class "Default")
      (node (ref "BAT1") (pin "1") (pinfunction "+3V_1") (pintype "passive+no_connect"))
    )
    (net (code "94") (name "unconnected-(BAT1-GND-Pad2)") (class "Default")
      (node (ref "BAT1") (pin "2") (pinfunction "GND_2") (pintype "passive+no_connect"))
    )
    (net (code "95") (name "unconnected-(IC2-CBUS0-Pad23)") (class "Default")
      (node (ref "IC2") (pin "23") (pinfunction "CBUS0_23") (pintype "passive+no_connect"))
    )
    (net (code "96") (name "unconnected-(IC2-CBUS1-Pad22)") (class "Default")
      (node (ref "IC2") (pin "22") (pinfunction "CBUS1_22") (pintype "passive+no_connect"))
    )
    (net (code "97") (name "unconnected-(IC2-CBUS2-Pad13)") (class "Default")
      (node (ref "IC2") (pin "13") (pinfunction "CBUS2_13") (pintype "passive+no_connect"))
    )
    (net (code "98") (name "unconnected-(IC2-CBUS3-Pad12)") (class "Default")
      (node (ref "IC2") (pin "12") (pinfunction "CBUS3_12") (pintype "passive+no_connect"))
    )
    (net (code "99") (name "unconnected-(IC2-CBUS3-Pad14)") (class "Default")
      (node (ref "IC2") (pin "14") (pinfunction "CBUS3_14") (pintype "passive+no_connect"))
    )
    (net (code "100") (name "unconnected-(IC2-CTS#-Pad11)") (class "Default")
      (node (ref "IC2") (pin "11") (pinfunction "CTS#_11") (pintype "passive+no_connect"))
    )
    (net (code "101") (name "unconnected-(IC2-DCD#-Pad10)") (class "Default")
      (node (ref "IC2") (pin "10") (pinfunction "DCD#_10") (pintype "passive+no_connect"))
    )
    (net (code "102") (name "unconnected-(IC2-DSR#-Pad9)") (class "Default")
      (node (ref "IC2") (pin "9") (pinfunction "DSR#_9") (pintype "passive+no_connect"))
    )
    (net (code "103") (name "unconnected-(IC2-DTR#-Pad2)") (class "Default")
      (node (ref "IC2") (pin "2") (pinfunction "DTR#_2") (pintype "passive+no_connect"))
    )
    (net (code "104") (name "unconnected-(IC2-NC-Pad8)") (class "Default")
      (node (ref "IC2") (pin "8") (pinfunction "NC_8") (pintype "passive+no_connect"))
    )
    (net (code "105") (name "unconnected-(IC2-NC-Pad24)") (class "Default")
      (node (ref "IC2") (pin "24") (pinfunction "NC_24") (pintype "passive+no_connect"))
    )
    (net (code "106") (name "unconnected-(IC2-OSCI-Pad27)") (class "Default")
      (node (ref "IC2") (pin "27") (pinfunction "OSCI_27") (pintype "passive+no_connect"))
    )
    (net (code "107") (name "unconnected-(IC2-OSCO-Pad28)") (class "Default")
      (node (ref "IC2") (pin "28") (pinfunction "OSCO_28") (pintype "passive+no_connect"))
    )
    (net (code "108") (name "unconnected-(IC2-RESET#-Pad19)") (class "Default")
      (node (ref "IC2") (pin "19") (pinfunction "RESET#_19") (pintype "passive+no_connect"))
    )
    (net (code "109") (name "unconnected-(IC2-RI#-Pad6)") (class "Default")
      (node (ref "IC2") (pin "6") (pinfunction "RI#_6") (pintype "passive+no_connect"))
    )
    (net (code "110") (name "unconnected-(IC2-RTS#-Pad3)") (class "Default")
      (node (ref "IC2") (pin "3") (pinfunction "RTS#_3") (pintype "passive+no_connect"))
    )
    (net (code "111") (name "unconnected-(J1-CC1_A-PadA5)") (class "Default")
      (node (ref "J1") (pin "A5") (pinfunction "CC1_A_A5") (pintype "bidirectional"))
    )
    (net (code "112") (name "unconnected-(J1-CC2_B-PadB5)") (class "Default")
      (node (ref "J1") (pin "B5") (pinfunction "CC2_B_B5") (pintype "bidirectional"))
    )
    (net (code "113") (name "unconnected-(J1-SBU1-PadA8)") (class "Default")
      (node (ref "J1") (pin "A8") (pinfunction "SBU1_A8") (pintype "bidirectional"))
    )
    (net (code "114") (name "unconnected-(J1-SBU2-PadB8)") (class "Default")
      (node (ref "J1") (pin "B8") (pinfunction "SBU2_B8") (pintype "bidirectional"))
    )
    (net (code "115") (name "unconnected-(U6-NC-Pad73)") (class "Default")
      (node (ref "U6") (pin "73") (pinfunction "NC_73") (pintype "passive"))
    )
    (net (code "116") (name "unconnected-(U6-PA11{slash}USART1_CTS{slash}USB_DM{slash}CAN_RX{slash}RIM1_CH4-Pad70)") (class "Default")
      (node (ref "U6") (pin "70") (pinfunction "PA11/USART1_CTS/USB_DM/CAN_RX/RIM1_CH4_70") (pintype "passive"))
    )
    (net (code "117") (name "unconnected-(U6-PA12{slash}USART1_RTS{slash}USB_DP{slash}CAN_TX{slash}TIM1_ETR-Pad71)") (class "Default")
      (node (ref "U6") (pin "71") (pinfunction "PA12/USART1_RTS/USB_DP/CAN_TX/TIM1_ETR_71") (pintype "passive"))
    )
    (net (code "118") (name "unconnected-(U6-PA15{slash}JTDI{slash}SPI3_NSS{slash}I2S3_WS{slash}TIM2_CH1_ETR-Pad77)") (class "Default")
      (node (ref "U6") (pin "77") (pinfunction "PA15/JTDI/SPI3_NSS/I2S3_WS/TIM2_CH1_ETR_77") (pintype "passive"))
    )
    (net (code "119") (name "unconnected-(U6-PC13{slash}TAMPER-RTC-Pad7)") (class "Default")
      (node (ref "U6") (pin "7") (pinfunction "PC13/TAMPER-RTC_7") (pintype "passive"))
    )
    (net (code "120") (name "unconnected-(U6-PD0{slash}OSC_IN{slash}FSMC_D2{slash}CAN_RX-Pad81)") (class "Default")
      (node (ref "U6") (pin "81") (pinfunction "PD0/OSC_IN/FSMC_D2/CAN_RX_81") (pintype "passive"))
    )
    (net (code "121") (name "unconnected-(U6-PD1{slash}OSC_OUT{slash}FSMC_D3{slash}CAN_TX-Pad82)") (class "Default")
      (node (ref "U6") (pin "82") (pinfunction "PD1/OSC_OUT/FSMC_D3/CAN_TX_82") (pintype "passive"))
    )
    (net (code "122") (name "unconnected-(U6-PD3{slash}FSMC_CLK{slash}USART2_CTS-Pad84)") (class "Default")
      (node (ref "U6") (pin "84") (pinfunction "PD3/FSMC_CLK/USART2_CTS_84") (pintype "passive"))
    )
    (net (code "123") (name "unconnected-(U6-PD4{slash}FSMC_NOE{slash}USART2_RTS-Pad85)") (class "Default")
      (node (ref "U6") (pin "85") (pinfunction "PD4/FSMC_NOE/USART2_RTS_85") (pintype "passive"))
    )
    (net (code "124") (name "unconnected-(U6-PE2{slash}TRACECK{slash}FSMC_A23-Pad1)") (class "Default")
      (node (ref "U6") (pin "1") (pinfunction "PE2/TRACECK/FSMC_A23_1") (pintype "passive"))
    )
    (net (code "125") (name "unconnected-(U6-PE3{slash}TRACED0{slash}FSMC_A19-Pad2)") (class "Default")
      (node (ref "U6") (pin "2") (pinfunction "PE3/TRACED0/FSMC_A19_2") (pintype "passive"))
    )
    (net (code "126") (name "unconnected-(U6-PE4{slash}TRCED1{slash}FSMC_A20-Pad3)") (class "Default")
      (node (ref "U6") (pin "3") (pinfunction "PE4/TRCED1/FSMC_A20_3") (pintype "passive"))
    )
    (net (code "127") (name "unconnected-(U6-PE5{slash}TRACED2{slash}FSMC_A21-Pad4)") (class "Default")
      (node (ref "U6") (pin "4") (pinfunction "PE5/TRACED2/FSMC_A21_4") (pintype "passive"))
    )
    (net (code "128") (name "unconnected-(U6-PE6{slash}TRACED3{slash}FSMC_A22-Pad5)") (class "Default")
      (node (ref "U6") (pin "5") (pinfunction "PE6/TRACED3/FSMC_A22_5") (pintype "passive"))
    )
  )
)
